# microcontroller.net
KiCad netlist of a schematic drawn in Altium Designer
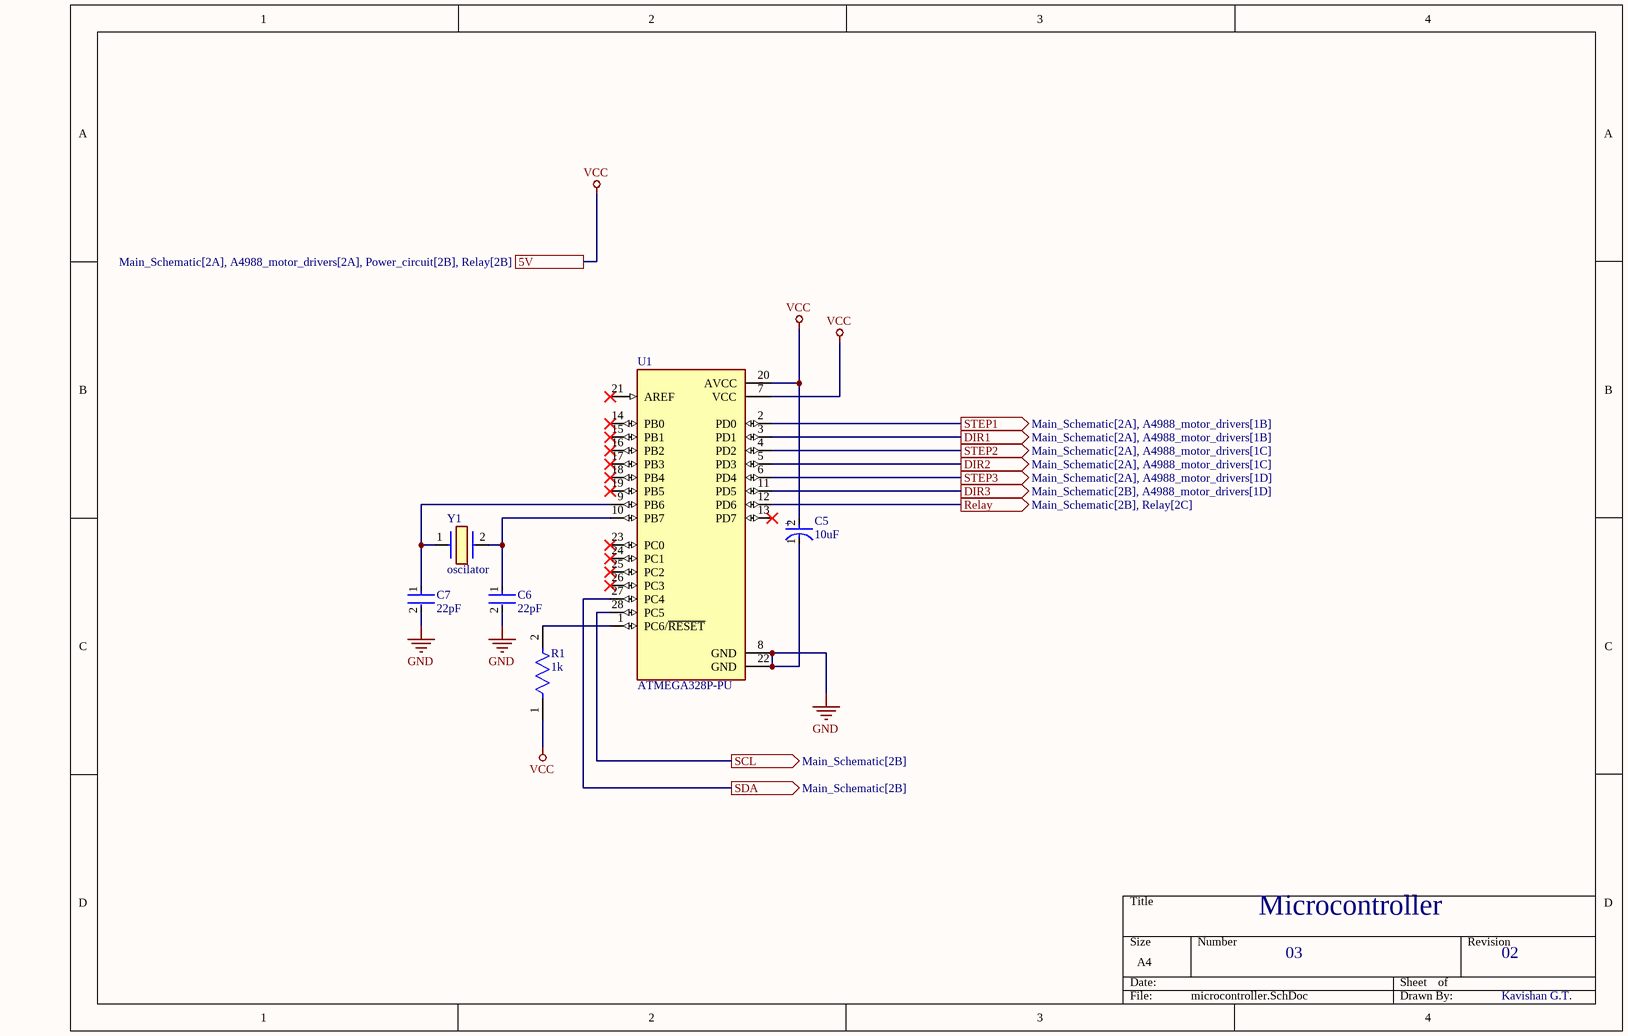
[diagram p0: microcontroller.SchDoc]

(export (version "E")
  (design (tool "Eeschema 10.0.6"))
  (components
    (comp (ref "C5")
      (value "10uF")
      (footprint "FP-RAD-TH-D_12_5_0_5-L_20-MFG")
      (description "Aluminum Electrolytic Capacitors (Radial Lead Type) 10uF ±20% 450V")
      (fields (field (name "VOLTAGE") "450V") (field (name "TOLERANCE") "20%"))
      (libsource (lib "Altium Content Vault") (part "a00bbbee19879c290e62620ae7e47b1"))
    )
    (comp (ref "C6")
      (value "22pF")
      (footprint "FP-RCE0K1-MFG")
      (description "Cap Ceramic 22pF 50V C0G ±5% Radial 5mm +125°C Automotive Bulk")
      (fields (field (name "TOLERANCE") "5%"))
      (libsource (lib "Altium Content Vault") (part "b4654b650e69147ec39a6b967a45e02"))
    )
    (comp (ref "C7")
      (value "22pF")
      (footprint "FP-RCE0K1-MFG")
      (description "Cap Ceramic 22pF 50V C0G ±5% Radial 5mm +125°C Automotive Bulk")
      (fields (field (name "TOLERANCE") "5%"))
      (libsource (lib "Altium Content Vault") (part "b4654b650e69147ec39a6b967a45e02"))
    )
    (comp (ref "R1")
      (value "1k")
      (footprint "FP-MFR-25-MFG")
      (description "RES 1.18K OHM 1/4W 1% AXIAL")
      (fields (field (name "MANUFACTURER") "Yageo") (field (name "TOLERANCE") "1%"))
      (libsource (lib "Altium Content Vault") (part "1029c3af85768c4190bb7ad29bc67b5"))
    )
    (comp (ref "U1")
      (value "ATMEGA328P-PU")
      (footprint "DIP794W46P254L2967H457Q28B")
      (description "ATmega Series 20 MHz 32 KB Flash 2 KB SRAM 8-Bit Microcontroller - DIP-28")
      (libsource (lib "ATMEGA328P-PU") (part "ATMEGA328P-PU"))
    )
    (comp (ref "Y1")
      (value "oscilator")
      (footprint "SamacSys:HC49USFF5F1816000MHZ")
      (description "Crystal or Oscillator")
      (fields (field (name "MANUFACTURER_PART_NUMBER") "HC49US-FF5F18-16.000MHZ"))
      (libsource (lib "*") (part "HC49US-FF5F18-16.000MHZ"))
    )
  )
  (nets
    (net (code "1") (name "/DIR1") (class "Default")
      (node (ref "U1") (pin "3") (pinfunction "PD1_3") (pintype "bidirectional"))
    )
    (net (code "2") (name "/DIR2") (class "Default")
      (node (ref "U1") (pin "5") (pinfunction "PD3_5") (pintype "bidirectional"))
    )
    (net (code "3") (name "/DIR3") (class "Default")
      (node (ref "U1") (pin "11") (pinfunction "PD5_11") (pintype "bidirectional"))
    )
    (net (code "4") (name "/Relay") (class "Default")
      (node (ref "U1") (pin "12") (pinfunction "PD6_12") (pintype "bidirectional"))
    )
    (net (code "5") (name "/SCL") (class "Default")
      (node (ref "U1") (pin "28") (pinfunction "PC5_28") (pintype "bidirectional"))
    )
    (net (code "6") (name "/SDA") (class "Default")
      (node (ref "U1") (pin "27") (pinfunction "PC4_27") (pintype "bidirectional"))
    )
    (net (code "7") (name "/STEP1") (class "Default")
      (node (ref "U1") (pin "2") (pinfunction "PD0_2") (pintype "bidirectional"))
    )
    (net (code "8") (name "/STEP2") (class "Default")
      (node (ref "U1") (pin "4") (pinfunction "PD2_4") (pintype "bidirectional"))
    )
    (net (code "9") (name "/STEP3") (class "Default")
      (node (ref "U1") (pin "6") (pinfunction "PD4_6") (pintype "bidirectional"))
    )
    (net (code "10") (name "GND") (class "Default")
      (node (ref "C5") (pin "1") (pinfunction "C_1") (pintype "passive"))
      (node (ref "C6") (pin "2") (pinfunction "2_2") (pintype "passive"))
      (node (ref "C7") (pin "2") (pinfunction "2_2") (pintype "passive"))
      (node (ref "U1") (pin "22") (pinfunction "GND_22") (pintype "power_in"))
      (node (ref "U1") (pin "8") (pinfunction "GND_8") (pintype "power_in"))
    )
    (net (code "11") (name "Net-(U1-PB6)") (class "Default")
      (node (ref "C7") (pin "1") (pinfunction "1_1") (pintype "passive"))
      (node (ref "U1") (pin "9") (pinfunction "PB6_9") (pintype "bidirectional"))
      (node (ref "Y1") (pin "1") (pinfunction "1_1") (pintype "passive"))
    )
    (net (code "12") (name "Net-(U1-PB7)") (class "Default")
      (node (ref "C6") (pin "1") (pinfunction "1_1") (pintype "passive"))
      (node (ref "U1") (pin "10") (pinfunction "PB7_10") (pintype "bidirectional"))
      (node (ref "Y1") (pin "2") (pinfunction "2_2") (pintype "passive"))
    )
    (net (code "13") (name "Net-(U1-PC6{slash}~{RESET})") (class "Default")
      (node (ref "R1") (pin "2") (pinfunction "2_2") (pintype "passive"))
      (node (ref "U1") (pin "1") (pinfunction "PC6/~{RESET}_1") (pintype "bidirectional"))
    )
    (net (code "14") (name "VCC") (class "Default")
      (node (ref "C5") (pin "2") (pinfunction "A_2") (pintype "passive"))
      (node (ref "R1") (pin "1") (pinfunction "1_1") (pintype "passive"))
      (node (ref "U1") (pin "20") (pinfunction "AVCC_20") (pintype "power_in"))
      (node (ref "U1") (pin "7") (pinfunction "VCC_7") (pintype "power_in"))
    )
    (net (code "15") (name "unconnected-(U1-AREF-Pad21)") (class "Default")
      (node (ref "U1") (pin "21") (pinfunction "AREF_21") (pintype "input+no_connect"))
    )
    (net (code "16") (name "unconnected-(U1-PB0-Pad14)") (class "Default")
      (node (ref "U1") (pin "14") (pinfunction "PB0_14") (pintype "bidirectional+no_connect"))
    )
    (net (code "17") (name "unconnected-(U1-PB1-Pad15)") (class "Default")
      (node (ref "U1") (pin "15") (pinfunction "PB1_15") (pintype "bidirectional+no_connect"))
    )
    (net (code "18") (name "unconnected-(U1-PB2-Pad16)") (class "Default")
      (node (ref "U1") (pin "16") (pinfunction "PB2_16") (pintype "bidirectional+no_connect"))
    )
    (net (code "19") (name "unconnected-(U1-PB3-Pad17)") (class "Default")
      (node (ref "U1") (pin "17") (pinfunction "PB3_17") (pintype "bidirectional+no_connect"))
    )
    (net (code "20") (name "unconnected-(U1-PB4-Pad18)") (class "Default")
      (node (ref "U1") (pin "18") (pinfunction "PB4_18") (pintype "bidirectional+no_connect"))
    )
    (net (code "21") (name "unconnected-(U1-PB5-Pad19)") (class "Default")
      (node (ref "U1") (pin "19") (pinfunction "PB5_19") (pintype "bidirectional+no_connect"))
    )
    (net (code "22") (name "unconnected-(U1-PC0-Pad23)") (class "Default")
      (node (ref "U1") (pin "23") (pinfunction "PC0_23") (pintype "bidirectional+no_connect"))
    )
    (net (code "23") (name "unconnected-(U1-PC1-Pad24)") (class "Default")
      (node (ref "U1") (pin "24") (pinfunction "PC1_24") (pintype "bidirectional+no_connect"))
    )
    (net (code "24") (name "unconnected-(U1-PC2-Pad25)") (class "Default")
      (node (ref "U1") (pin "25") (pinfunction "PC2_25") (pintype "bidirectional+no_connect"))
    )
    (net (code "25") (name "unconnected-(U1-PC3-Pad26)") (class "Default")
      (node (ref "U1") (pin "26") (pinfunction "PC3_26") (pintype "bidirectional+no_connect"))
    )
    (net (code "26") (name "unconnected-(U1-PD7-Pad13)") (class "Default")
      (node (ref "U1") (pin "13") (pinfunction "PD7_13") (pintype "bidirectional+no_connect"))
    )
  )
)
